# DB3AC_Fldigi_Baofeng_V02.net
KiCad netlist of a schematic drawn in EAGLE
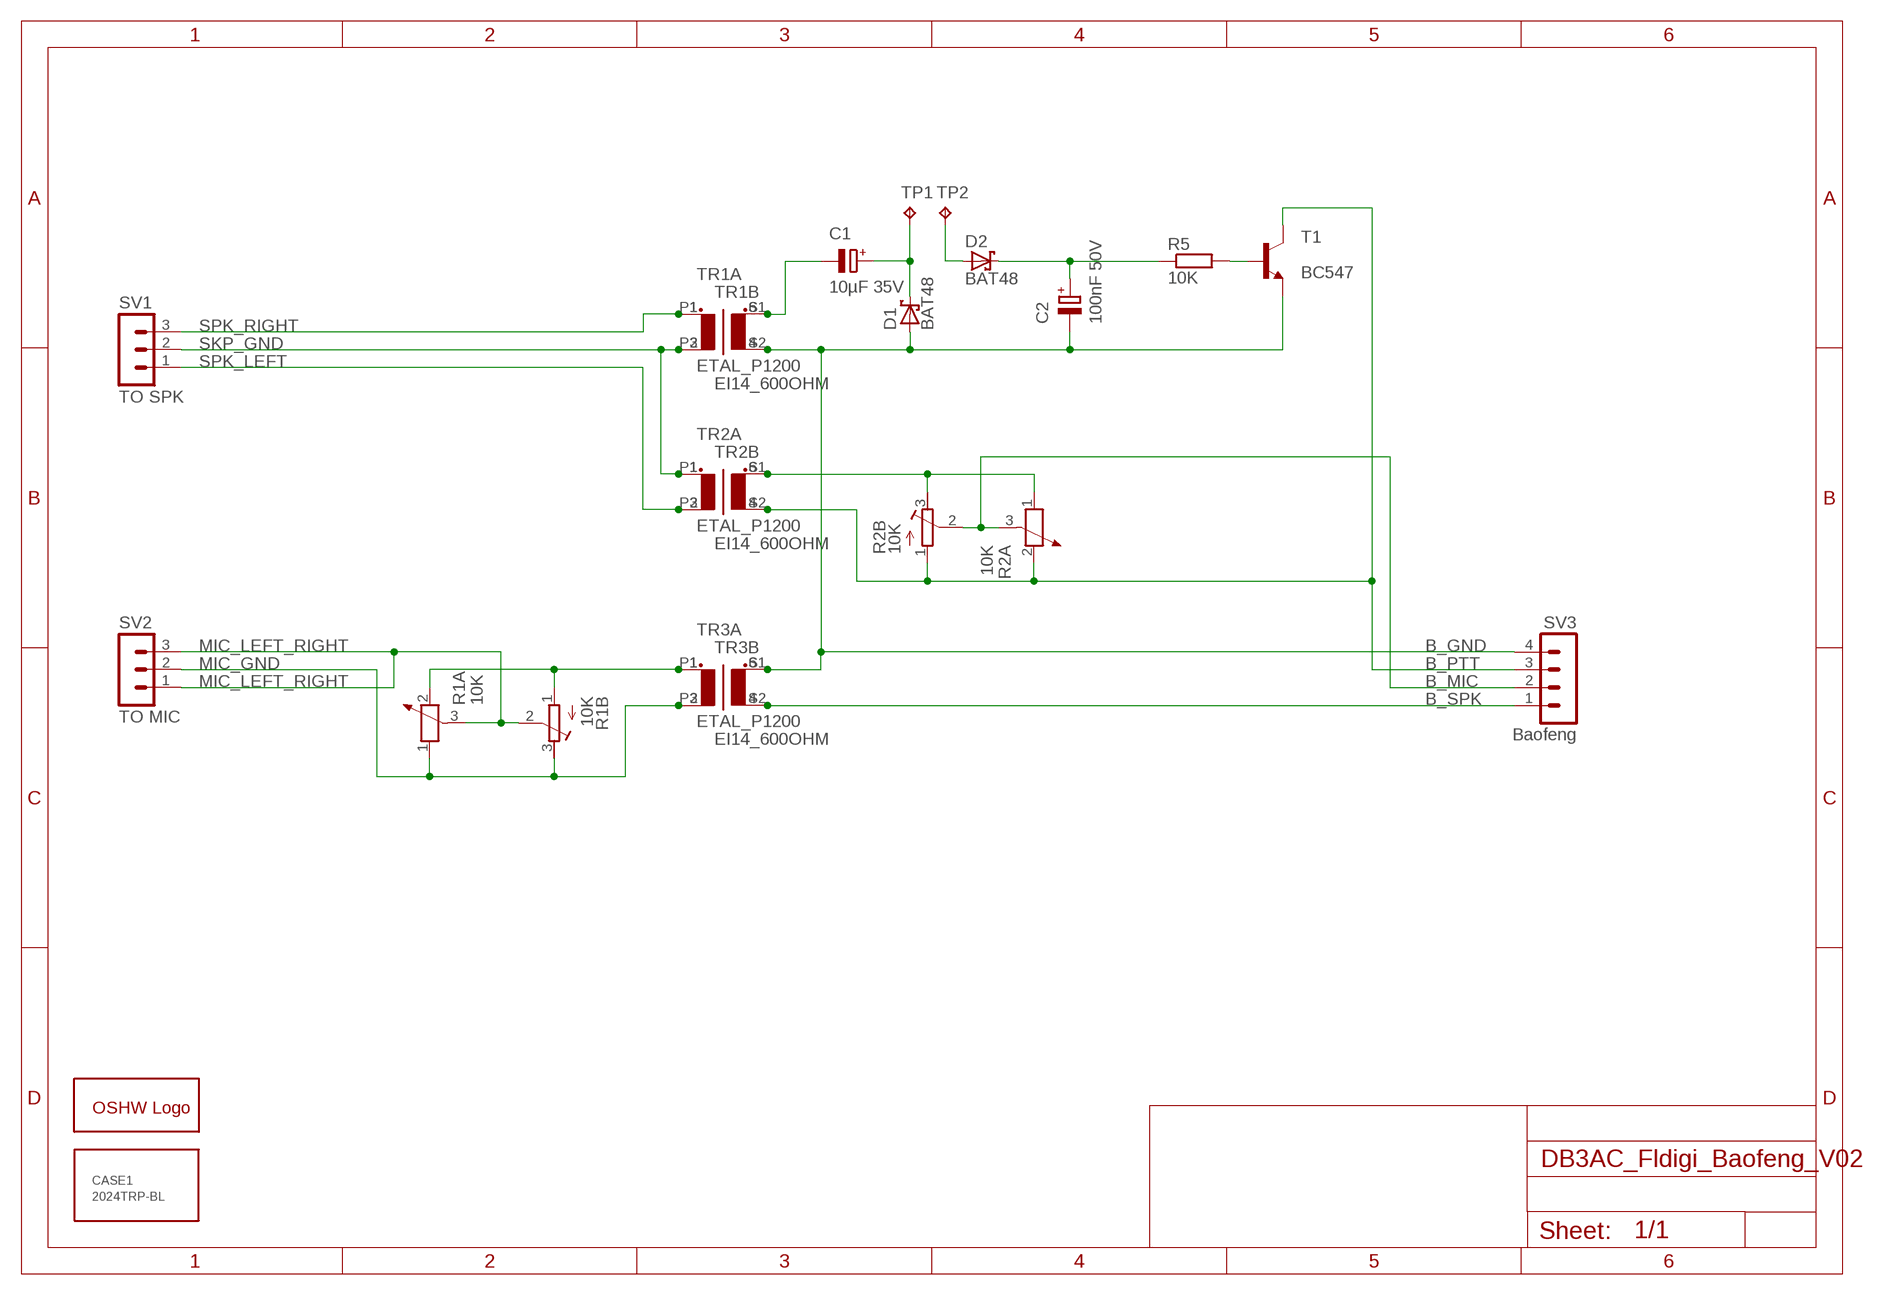
[diagram p0: schematic, sheet 1]

(export (version "E")
  (design (tool "Eeschema 10.0.6"))
  (components
    (comp (ref "C1")
      (value "10µF 35V")
      (footprint "eagle-import:E2,5-7")
      (libsource (lib "eagle-import") (part "CPOL-EUE2.5-7"))
    )
    (comp (ref "C2")
      (value "100nF 50V")
      (footprint "eagle-import:E2,5-7")
      (libsource (lib "eagle-import") (part "CPOL-EUE2.5-7"))
    )
    (comp (ref "CASE1")
      (value "2024TRP-BL")
      (footprint "eagle-import:2024")
      (libsource (lib "eagle-import") (part "2024TRP-BL"))
    )
    (comp (ref "D1")
      (value "BAT48")
      (footprint "eagle-import:DO35-10")
      (libsource (lib "eagle-import") (part "BAT42"))
    )
    (comp (ref "D2")
      (value "BAT48")
      (footprint "eagle-import:DO35-10")
      (libsource (lib "eagle-import") (part "BAT42"))
    )
    (comp (ref "GOLD_ORB_SM1")
      (value "OSHWLOGOLOGO8MM")
      (footprint "eagle-import:OSHW_8MM")
      (libsource (lib "eagle-import") (part "OSHWLOGOLOGO8MM"))
    )
    (comp (ref "R1A")
      (value "10K")
      (footprint "eagle-import:PT-10")
      (libsource (lib "eagle-import") (part "POTENTIOMETER_PT-10"))
    )
    (comp (ref "R1B")
      (value "10K")
      (footprint "eagle-import:RTRIM3339P")
      (libsource (lib "eagle-import") (part "R-TRIMM3339P"))
    )
    (comp (ref "R2A")
      (value "10K")
      (footprint "eagle-import:PT-10")
      (libsource (lib "eagle-import") (part "POTENTIOMETER_PT-10"))
    )
    (comp (ref "R2B")
      (value "10K")
      (footprint "eagle-import:RTRIM3339P")
      (libsource (lib "eagle-import") (part "R-TRIMM3339P"))
    )
    (comp (ref "R5")
      (value "10K")
      (footprint "eagle-import:0204_7")
      (libsource (lib "eagle-import") (part "R-EU_0204/7"))
    )
    (comp (ref "SV1")
      (value "TO SPK")
      (footprint "eagle-import:MA03-1")
      (libsource (lib "eagle-import") (part "MA03-1"))
    )
    (comp (ref "SV2")
      (value "TO MIC")
      (footprint "eagle-import:MA03-1")
      (libsource (lib "eagle-import") (part "MA03-1"))
    )
    (comp (ref "SV3")
      (value "Baofeng")
      (footprint "eagle-import:MA04-1")
      (libsource (lib "eagle-import") (part "MA04-1"))
    )
    (comp (ref "T1")
      (value "BC547")
      (footprint "eagle-import:TO92-CBE")
      (libsource (lib "eagle-import") (part "-NPN-TO92-CBEBC547"))
    )
    (comp (ref "TP1")
      (value "TPPAD1-13Y")
      (footprint "eagle-import:P1-13Y")
      (libsource (lib "eagle-import") (part "TPPAD1-13Y"))
    )
    (comp (ref "TP2")
      (value "TPPAD1-13Y")
      (footprint "eagle-import:P1-13Y")
      (libsource (lib "eagle-import") (part "TPPAD1-13Y"))
    )
    (comp (ref "TR1A")
      (value "ETAL_P1200")
      (footprint "eagle-import:ETAL_P1200")
      (fields (field (name "MPN") "P1200"))
      (libsource (lib "eagle-import") (part "ETAL_P1200"))
    )
    (comp (ref "TR1B")
      (value "EI14_600OHM")
      (footprint "eagle-import:EI14")
      (libsource (lib "eagle-import") (part "EI14_600OHM"))
    )
    (comp (ref "TR2A")
      (value "ETAL_P1200")
      (footprint "eagle-import:ETAL_P1200")
      (fields (field (name "MPN") "P1200"))
      (libsource (lib "eagle-import") (part "ETAL_P1200"))
    )
    (comp (ref "TR2B")
      (value "EI14_600OHM")
      (footprint "eagle-import:EI14")
      (libsource (lib "eagle-import") (part "EI14_600OHM"))
    )
    (comp (ref "TR3A")
      (value "ETAL_P1200")
      (footprint "eagle-import:ETAL_P1200")
      (fields (field (name "MPN") "P1200"))
      (libsource (lib "eagle-import") (part "ETAL_P1200"))
    )
    (comp (ref "TR3B")
      (value "EI14_600OHM")
      (footprint "eagle-import:EI14")
      (libsource (lib "eagle-import") (part "EI14_600OHM"))
    )
  )
  (nets
    (net (code "1") (name "/B_GND") (class "Default")
      (node (ref "C2") (pin "-") (pinfunction "-_-") (pintype "passive"))
      (node (ref "D1") (pin "A") (pinfunction "A_A") (pintype "passive"))
      (node (ref "SV3") (pin "4") (pinfunction "4_4") (pintype "passive"))
      (node (ref "T1") (pin "E") (pinfunction "E_E") (pintype "passive"))
      (node (ref "TR1A") (pin "4") (pinfunction "S2_4") (pintype "passive"))
      (node (ref "TR1B") (pin "S2") (pinfunction "S2_S2") (pintype "passive"))
      (node (ref "TR3A") (pin "6") (pinfunction "S1_6") (pintype "passive"))
      (node (ref "TR3B") (pin "S1") (pinfunction "S1_S1") (pintype "passive"))
    )
    (net (code "2") (name "/B_MIC") (class "Default")
      (node (ref "R2A") (pin "3") (pinfunction "3_3") (pintype "passive"))
      (node (ref "R2B") (pin "2") (pinfunction "S_2") (pintype "passive"))
      (node (ref "SV3") (pin "2") (pinfunction "2_2") (pintype "passive"))
    )
    (net (code "3") (name "/B_PTT") (class "Default")
      (node (ref "R2A") (pin "2") (pinfunction "2_2") (pintype "passive"))
      (node (ref "R2B") (pin "1") (pinfunction "A_1") (pintype "passive"))
      (node (ref "SV3") (pin "3") (pinfunction "3_3") (pintype "passive"))
      (node (ref "T1") (pin "C") (pinfunction "C_C") (pintype "passive"))
      (node (ref "TR2A") (pin "4") (pinfunction "S2_4") (pintype "passive"))
      (node (ref "TR2B") (pin "S2") (pinfunction "S2_S2") (pintype "passive"))
    )
    (net (code "4") (name "/B_SPK") (class "Default")
      (node (ref "SV3") (pin "1") (pinfunction "1_1") (pintype "passive"))
      (node (ref "TR3A") (pin "4") (pinfunction "S2_4") (pintype "passive"))
      (node (ref "TR3B") (pin "S2") (pinfunction "S2_S2") (pintype "passive"))
    )
    (net (code "5") (name "/MIC_GND") (class "Default")
      (node (ref "R1A") (pin "1") (pinfunction "1_1") (pintype "passive"))
      (node (ref "R1B") (pin "3") (pinfunction "E_3") (pintype "passive"))
      (node (ref "SV2") (pin "2") (pinfunction "2_2") (pintype "passive"))
      (node (ref "TR3A") (pin "3") (pinfunction "P2_3") (pintype "passive"))
      (node (ref "TR3B") (pin "P2") (pinfunction "P2_P2") (pintype "passive"))
    )
    (net (code "6") (name "/MIC_LEFT_RIGHT") (class "Default")
      (node (ref "R1A") (pin "3") (pinfunction "3_3") (pintype "passive"))
      (node (ref "R1B") (pin "2") (pinfunction "S_2") (pintype "passive"))
      (node (ref "SV2") (pin "1") (pinfunction "1_1") (pintype "passive"))
      (node (ref "SV2") (pin "3") (pinfunction "3_3") (pintype "passive"))
    )
    (net (code "7") (name "/SKP_GND") (class "Default")
      (node (ref "SV1") (pin "2") (pinfunction "2_2") (pintype "passive"))
      (node (ref "TR1A") (pin "3") (pinfunction "P2_3") (pintype "passive"))
      (node (ref "TR1B") (pin "P2") (pinfunction "P2_P2") (pintype "passive"))
      (node (ref "TR2A") (pin "1") (pinfunction "P1_1") (pintype "passive"))
      (node (ref "TR2B") (pin "P1") (pinfunction "P1_P1") (pintype "passive"))
    )
    (net (code "8") (name "/SPK_LEFT") (class "Default")
      (node (ref "SV1") (pin "1") (pinfunction "1_1") (pintype "passive"))
      (node (ref "TR2A") (pin "3") (pinfunction "P2_3") (pintype "passive"))
      (node (ref "TR2B") (pin "P2") (pinfunction "P2_P2") (pintype "passive"))
    )
    (net (code "9") (name "/SPK_RIGHT") (class "Default")
      (node (ref "SV1") (pin "3") (pinfunction "3_3") (pintype "passive"))
      (node (ref "TR1A") (pin "1") (pinfunction "P1_1") (pintype "passive"))
      (node (ref "TR1B") (pin "P1") (pinfunction "P1_P1") (pintype "passive"))
    )
    (net (code "10") (name "Net-(C1-Pad+)") (class "Default")
      (node (ref "C1") (pin "+") (pinfunction "+_+") (pintype "passive"))
      (node (ref "D1") (pin "C") (pinfunction "C_C") (pintype "passive"))
      (node (ref "TP1") (pin "TP") (pinfunction "TP_TP") (pintype "input"))
    )
    (net (code "11") (name "Net-(C2-Pad+)") (class "Default")
      (node (ref "C2") (pin "+") (pinfunction "+_+") (pintype "passive"))
      (node (ref "D2") (pin "C") (pinfunction "C_C") (pintype "passive"))
      (node (ref "R5") (pin "1") (pinfunction "1_1") (pintype "passive"))
    )
    (net (code "12") (name "Net-(D2-PadA)") (class "Default")
      (node (ref "D2") (pin "A") (pinfunction "A_A") (pintype "passive"))
      (node (ref "TP2") (pin "TP") (pinfunction "TP_TP") (pintype "input"))
    )
    (net (code "13") (name "Net-(R1B-A)") (class "Default")
      (node (ref "R1A") (pin "2") (pinfunction "2_2") (pintype "passive"))
      (node (ref "R1B") (pin "1") (pinfunction "A_1") (pintype "passive"))
      (node (ref "TR3A") (pin "1") (pinfunction "P1_1") (pintype "passive"))
      (node (ref "TR3B") (pin "P1") (pinfunction "P1_P1") (pintype "passive"))
    )
    (net (code "14") (name "Net-(R2B-E)") (class "Default")
      (node (ref "R2A") (pin "1") (pinfunction "1_1") (pintype "passive"))
      (node (ref "R2B") (pin "3") (pinfunction "E_3") (pintype "passive"))
      (node (ref "TR2A") (pin "6") (pinfunction "S1_6") (pintype "passive"))
      (node (ref "TR2B") (pin "S1") (pinfunction "S1_S1") (pintype "passive"))
    )
    (net (code "15") (name "Net-(R5-Pad2)") (class "Default")
      (node (ref "R5") (pin "2") (pinfunction "2_2") (pintype "passive"))
      (node (ref "T1") (pin "B") (pinfunction "B_B") (pintype "passive"))
    )
    (net (code "16") (name "Net-(TR1A-S1)") (class "Default")
      (node (ref "C1") (pin "-") (pinfunction "-_-") (pintype "passive"))
      (node (ref "TR1A") (pin "6") (pinfunction "S1_6") (pintype "passive"))
      (node (ref "TR1B") (pin "S1") (pinfunction "S1_S1") (pintype "passive"))
    )
  )
)
